# Hornbill.net
KiCad netlist of a schematic drawn in EAGLE
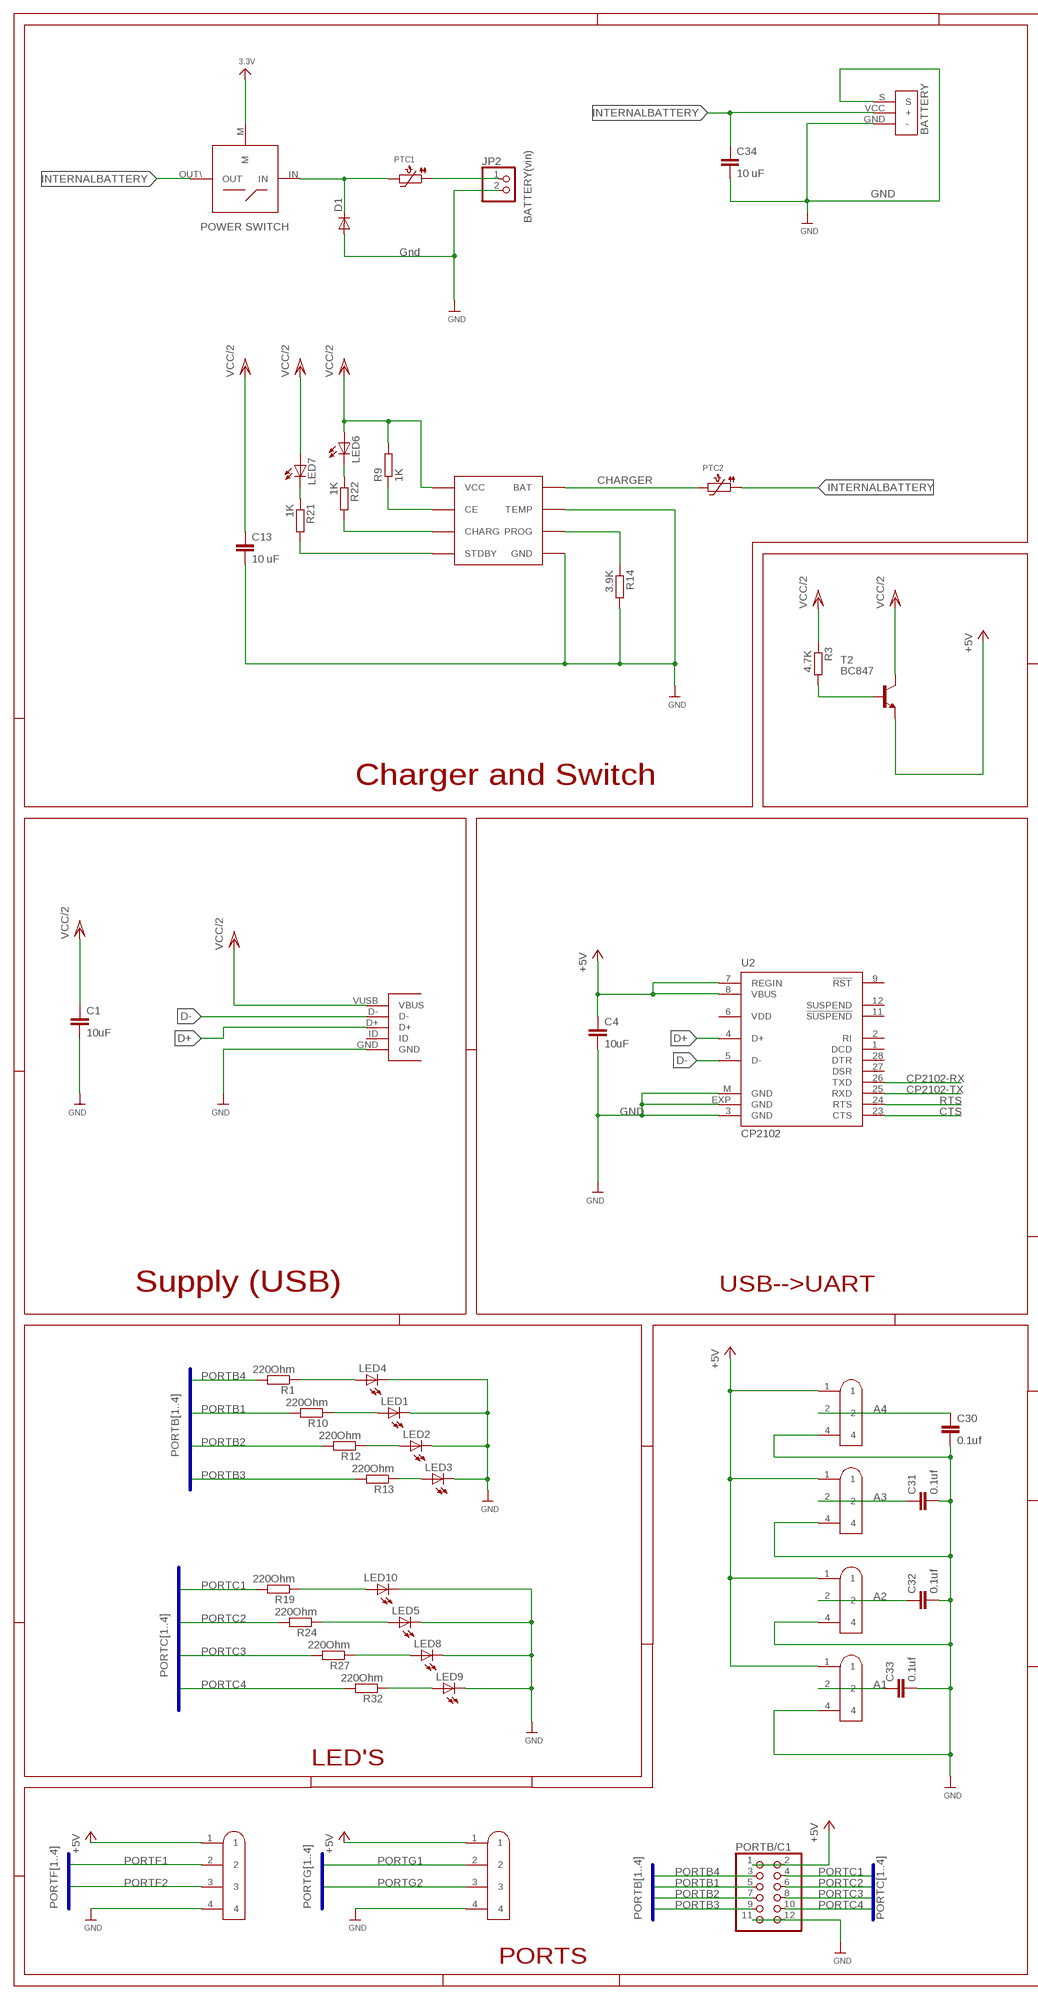
[diagram p0: schematic, sheet 1, part 1 of 2]
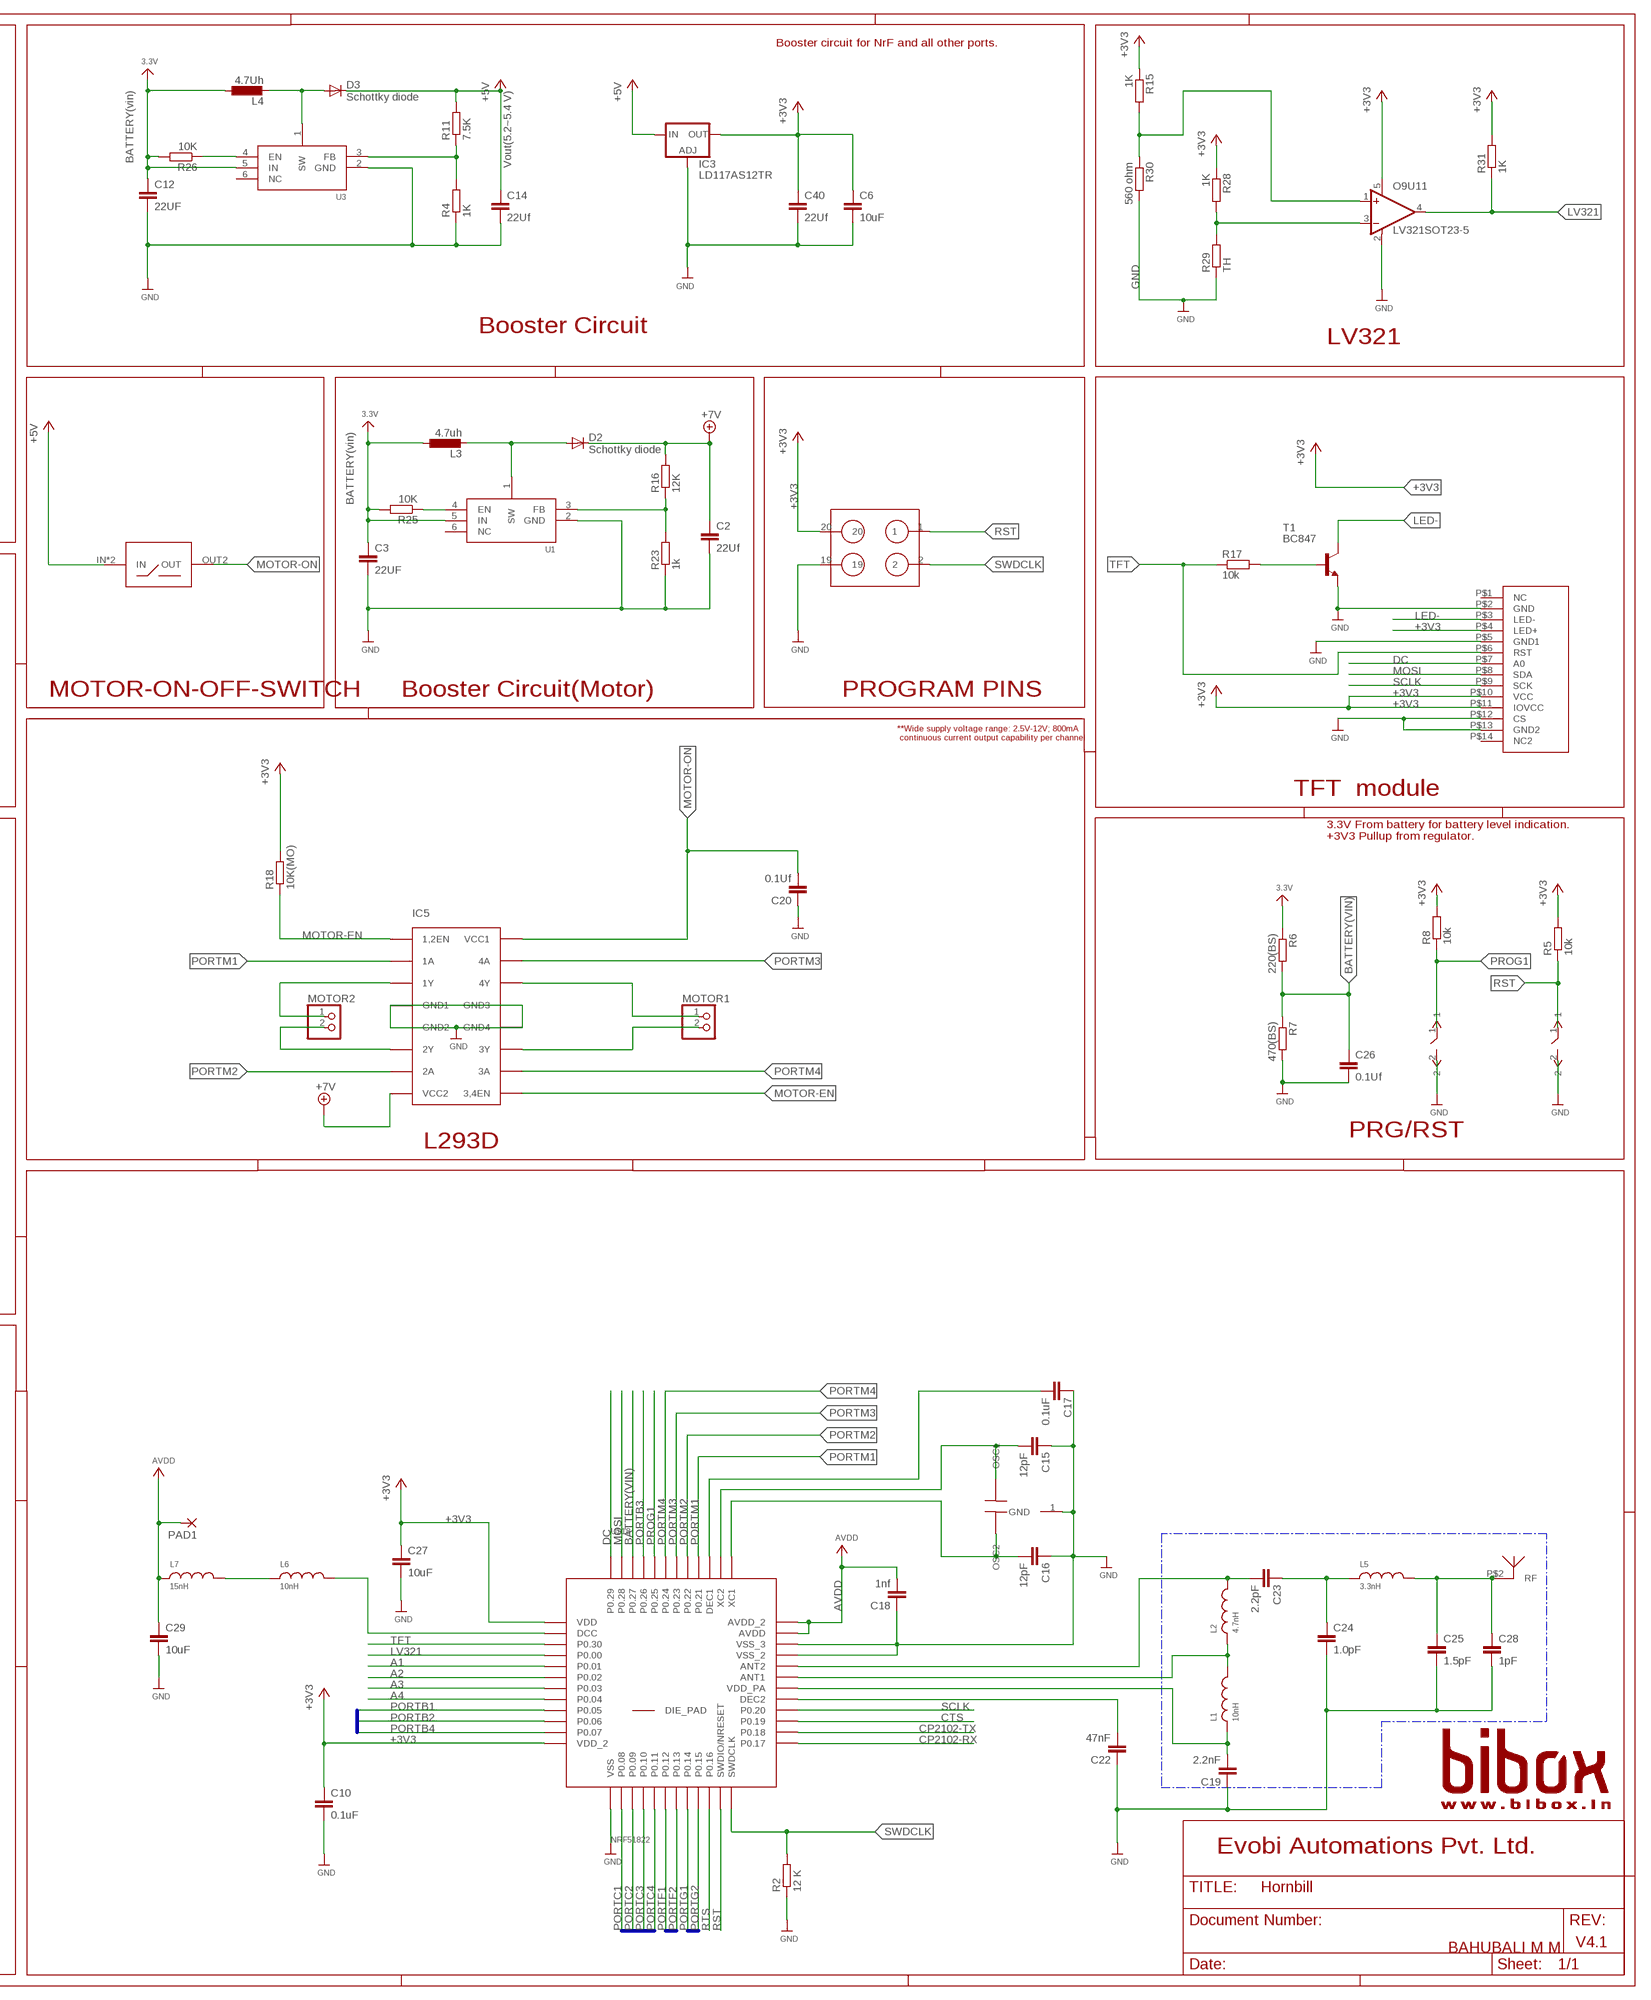
[diagram p1: schematic, sheet 1, part 2 of 2]

(export (version "E")
  (design (tool "Eeschema 10.0.6"))
  (components
    (comp (ref "BATTERY")
      (value "BS")
      (footprint "eagle-import:BS")
      (libsource (lib "eagle-import") (part "BS"))
    )
    (comp (ref "C1")
      (value "10uF")
      (footprint "eagle-import:0603")
      (libsource (lib "eagle-import") (part "CAP0603"))
    )
    (comp (ref "C2")
      (value "22Uf")
      (footprint "eagle-import:C0603")
      (libsource (lib "eagle-import") (part "C-EUC0603"))
    )
    (comp (ref "C3")
      (value "22UF")
      (footprint "eagle-import:C0603")
      (libsource (lib "eagle-import") (part "C-EUC0603"))
    )
    (comp (ref "C4")
      (value "10uF")
      (footprint "eagle-import:0603")
      (libsource (lib "eagle-import") (part "CAP0603"))
    )
    (comp (ref "C6")
      (value "10uF")
      (footprint "eagle-import:C0603")
      (libsource (lib "eagle-import") (part "C-EUC0603"))
    )
    (comp (ref "C10")
      (value "0.1uF")
      (footprint "eagle-import:C0603")
      (libsource (lib "eagle-import") (part "C-EUC0603"))
    )
    (comp (ref "C12")
      (value "22UF")
      (footprint "eagle-import:C0603")
      (libsource (lib "eagle-import") (part "C-EUC0603"))
    )
    (comp (ref "C13")
      (value "10 uF")
      (footprint "eagle-import:C0603")
      (libsource (lib "eagle-import") (part "C-EUC0603"))
    )
    (comp (ref "C14")
      (value "22Uf")
      (footprint "eagle-import:C0603")
      (libsource (lib "eagle-import") (part "C-EUC0603"))
    )
    (comp (ref "C15")
      (value "12pF")
      (footprint "eagle-import:C0603")
      (libsource (lib "eagle-import") (part "C-EUC0603"))
    )
    (comp (ref "C16")
      (value "12pF")
      (footprint "eagle-import:C0603")
      (libsource (lib "eagle-import") (part "C-EUC0603"))
    )
    (comp (ref "C17")
      (value "0.1uF")
      (footprint "eagle-import:C0603")
      (libsource (lib "eagle-import") (part "C-EUC0603"))
    )
    (comp (ref "C18")
      (value "1nf")
      (footprint "eagle-import:C0603")
      (libsource (lib "eagle-import") (part "C-EUC0603"))
    )
    (comp (ref "C19")
      (value "2.2nF")
      (footprint "eagle-import:C0603")
      (libsource (lib "eagle-import") (part "C-EUC0603"))
    )
    (comp (ref "C20")
      (value "0.1Uf")
      (footprint "eagle-import:C0603")
      (libsource (lib "eagle-import") (part "C-EUC0603"))
    )
    (comp (ref "C22")
      (value "47nF")
      (footprint "eagle-import:C0603")
      (libsource (lib "eagle-import") (part "C-EUC0603"))
    )
    (comp (ref "C23")
      (value "2.2pF")
      (footprint "eagle-import:C0603")
      (libsource (lib "eagle-import") (part "C-EUC0603"))
    )
    (comp (ref "C24")
      (value "1.0pF")
      (footprint "eagle-import:C0603")
      (libsource (lib "eagle-import") (part "C-EUC0603"))
    )
    (comp (ref "C25")
      (value "1.5pF")
      (footprint "eagle-import:C0603")
      (libsource (lib "eagle-import") (part "C-EUC0603"))
    )
    (comp (ref "C26")
      (value "0.1Uf")
      (footprint "eagle-import:C0603")
      (libsource (lib "eagle-import") (part "C-EUC0603"))
    )
    (comp (ref "C27")
      (value "10uF")
      (footprint "eagle-import:C0603")
      (libsource (lib "eagle-import") (part "C-EUC0603"))
    )
    (comp (ref "C28")
      (value "1pF")
      (footprint "eagle-import:C0603")
      (libsource (lib "eagle-import") (part "C-EUC0603"))
    )
    (comp (ref "C29")
      (value "10uF")
      (footprint "eagle-import:C0603")
      (libsource (lib "eagle-import") (part "C-EUC0603"))
    )
    (comp (ref "C30")
      (value "0.1uf")
      (footprint "eagle-import:C0603")
      (libsource (lib "eagle-import") (part "C-EUC0603"))
    )
    (comp (ref "C31")
      (value "0.1uf")
      (footprint "eagle-import:C0603")
      (libsource (lib "eagle-import") (part "C-EUC0603"))
    )
    (comp (ref "C32")
      (value "0.1uf")
      (footprint "eagle-import:C0603")
      (libsource (lib "eagle-import") (part "C-EUC0603"))
    )
    (comp (ref "C33")
      (value "0.1uf")
      (footprint "eagle-import:C0603")
      (libsource (lib "eagle-import") (part "C-EUC0603"))
    )
    (comp (ref "C34")
      (value "10 uF")
      (footprint "eagle-import:C0603")
      (libsource (lib "eagle-import") (part "C-EUC0603"))
    )
    (comp (ref "C40")
      (value "22Uf")
      (footprint "eagle-import:C0603")
      (libsource (lib "eagle-import") (part "C-EUC0603"))
    )
    (comp (ref "D1")
      (value "DIODESMA")
      (footprint "eagle-import:SMA-DIODE")
      (libsource (lib "eagle-import") (part "DIODESMA"))
    )
    (comp (ref "D2")
      (value "Schottky diode")
      (footprint "eagle-import:SMA-DIODE")
      (libsource (lib "eagle-import") (part "DIODESMA"))
    )
    (comp (ref "D3")
      (value "Schottky diode")
      (footprint "eagle-import:SMA-DIODE")
      (libsource (lib "eagle-import") (part "DIODESMA"))
    )
    (comp (ref "IC2")
      (value "LT1173CS8")
      (footprint "eagle-import:SOIC8")
      (libsource (lib "eagle-import") (part "LT1173CS8"))
    )
    (comp (ref "IC3")
      (value "LD117AS12TR")
      (footprint "eagle-import:SOT223")
      (libsource (lib "eagle-import") (part "LD117A?S12TR"))
    )
    (comp (ref "IC5")
      (value "L293D")
      (footprint "eagle-import:DIL16")
      (libsource (lib "eagle-import") (part "L293D"))
    )
    (comp (ref "JP2")
      (value "PINHD-1X2")
      (footprint "eagle-import:1X02")
      (libsource (lib "eagle-import") (part "PINHD-1X2"))
    )
    (comp (ref "L1")
      (value "10nH")
      (footprint "eagle-import:0603")
      (libsource (lib "eagle-import") (part "INDUCTOR0603"))
    )
    (comp (ref "L2")
      (value "4.7nH")
      (footprint "eagle-import:0603")
      (libsource (lib "eagle-import") (part "INDUCTOR0603"))
    )
    (comp (ref "L3")
      (value "4.7uh")
      (footprint "eagle-import:POWER-CHOKE_WE-TPC")
      (libsource (lib "eagle-import") (part "L-EUWE-TPC"))
    )
    (comp (ref "L4")
      (value "4.7Uh")
      (footprint "eagle-import:POWER-CHOKE_WE-TPC")
      (libsource (lib "eagle-import") (part "L-EUWE-TPC"))
    )
    (comp (ref "L5")
      (value "3.3nH")
      (footprint "eagle-import:0603")
      (libsource (lib "eagle-import") (part "INDUCTOR0603"))
    )
    (comp (ref "L6")
      (value "10nH")
      (footprint "eagle-import:0603")
      (libsource (lib "eagle-import") (part "INDUCTOR0603"))
    )
    (comp (ref "L7")
      (value "15nH")
      (footprint "eagle-import:0603")
      (libsource (lib "eagle-import") (part "INDUCTOR0603"))
    )
    (comp (ref "LED1")
      (value "LEDCHIP-LED0805")
      (footprint "eagle-import:CHIP-LED0805")
      (libsource (lib "eagle-import") (part "LEDCHIP-LED0805"))
    )
    (comp (ref "LED2")
      (value "LEDCHIP-LED0805")
      (footprint "eagle-import:CHIP-LED0805")
      (libsource (lib "eagle-import") (part "LEDCHIP-LED0805"))
    )
    (comp (ref "LED3")
      (value "LEDCHIP-LED0805")
      (footprint "eagle-import:CHIP-LED0805")
      (libsource (lib "eagle-import") (part "LEDCHIP-LED0805"))
    )
    (comp (ref "LED4")
      (value "LEDCHIP-LED0805")
      (footprint "eagle-import:CHIP-LED0805")
      (libsource (lib "eagle-import") (part "LEDCHIP-LED0805"))
    )
    (comp (ref "LED5")
      (value "LEDCHIP-LED0805")
      (footprint "eagle-import:CHIP-LED0805")
      (libsource (lib "eagle-import") (part "LEDCHIP-LED0805"))
    )
    (comp (ref "LED6")
      (value "LEDCHIP-LED0805")
      (footprint "eagle-import:CHIP-LED0805")
      (libsource (lib "eagle-import") (part "LEDCHIP-LED0805"))
    )
    (comp (ref "LED7")
      (value "LEDCHIP-LED0805")
      (footprint "eagle-import:CHIP-LED0805")
      (libsource (lib "eagle-import") (part "LEDCHIP-LED0805"))
    )
    (comp (ref "LED8")
      (value "LEDCHIP-LED0805")
      (footprint "eagle-import:CHIP-LED0805")
      (libsource (lib "eagle-import") (part "LEDCHIP-LED0805"))
    )
    (comp (ref "LED9")
      (value "LEDCHIP-LED0805")
      (footprint "eagle-import:CHIP-LED0805")
      (libsource (lib "eagle-import") (part "LEDCHIP-LED0805"))
    )
    (comp (ref "LED10")
      (value "LEDCHIP-LED0805")
      (footprint "eagle-import:CHIP-LED0805")
      (libsource (lib "eagle-import") (part "LEDCHIP-LED0805"))
    )
    (comp (ref "MOTOR1")
      (value "PINHD-1X2")
      (footprint "eagle-import:1X02")
      (libsource (lib "eagle-import") (part "PINHD-1X2"))
    )
    (comp (ref "MOTOR2")
      (value "PINHD-1X2")
      (footprint "eagle-import:1X02")
      (libsource (lib "eagle-import") (part "PINHD-1X2"))
    )
    (comp (ref "O9U11")
      (value "LV321SOT23-5")
      (footprint "eagle-import:SOT23-5")
      (libsource (lib "eagle-import") (part "LV321SOT23-5"))
    )
    (comp (ref "PAD1")
      (value "SMD2")
      (footprint "eagle-import:SMD1,27-2,54")
      (libsource (lib "eagle-import") (part "SMD2"))
    )
    (comp (ref "PORTB/C1")
      (value "PINHD-2X6")
      (footprint "eagle-import:2X06")
      (libsource (lib "eagle-import") (part "PINHD-2X6"))
    )
    (comp (ref "PTC1")
      (value "PTC1206")
      (footprint "eagle-import:1206")
      (libsource (lib "eagle-import") (part "PTC1206"))
    )
    (comp (ref "PTC2")
      (value "PTC1206")
      (footprint "eagle-import:1206")
      (libsource (lib "eagle-import") (part "PTC1206"))
    )
    (comp (ref "R1")
      (value "220Ohm")
      (footprint "eagle-import:R0603")
      (libsource (lib "eagle-import") (part "R-EU_R0603"))
    )
    (comp (ref "R2")
      (value "12 K")
      (footprint "eagle-import:R0603")
      (libsource (lib "eagle-import") (part "R-EU_R0603"))
    )
    (comp (ref "R3")
      (value "4.7K")
      (footprint "eagle-import:R0603")
      (libsource (lib "eagle-import") (part "R-EU_R0603"))
    )
    (comp (ref "R4")
      (value "1K")
      (footprint "eagle-import:R0603")
      (libsource (lib "eagle-import") (part "R-EU_R0603"))
    )
    (comp (ref "R5")
      (value "10k")
      (footprint "eagle-import:R0603")
      (libsource (lib "eagle-import") (part "R-EU_R0603"))
    )
    (comp (ref "R6")
      (value "220(BS)")
      (footprint "eagle-import:R0603")
      (libsource (lib "eagle-import") (part "R-EU_R0603"))
    )
    (comp (ref "R7")
      (value "470(BS)")
      (footprint "eagle-import:R0603")
      (libsource (lib "eagle-import") (part "R-EU_R0603"))
    )
    (comp (ref "R8")
      (value "10k")
      (footprint "eagle-import:R0603")
      (libsource (lib "eagle-import") (part "R-EU_R0603"))
    )
    (comp (ref "R9")
      (value "1K")
      (footprint "eagle-import:R0603")
      (libsource (lib "eagle-import") (part "R-EU_R0603"))
    )
    (comp (ref "R10")
      (value "220Ohm")
      (footprint "eagle-import:R0603")
      (libsource (lib "eagle-import") (part "R-EU_R0603"))
    )
    (comp (ref "R11")
      (value "7.5K")
      (footprint "eagle-import:R0603")
      (libsource (lib "eagle-import") (part "R-EU_R0603"))
    )
    (comp (ref "R12")
      (value "220Ohm")
      (footprint "eagle-import:R0603")
      (libsource (lib "eagle-import") (part "R-EU_R0603"))
    )
    (comp (ref "R13")
      (value "220Ohm")
      (footprint "eagle-import:R0603")
      (libsource (lib "eagle-import") (part "R-EU_R0603"))
    )
    (comp (ref "R14")
      (value "3.9K")
      (footprint "eagle-import:R0603")
      (libsource (lib "eagle-import") (part "R-EU_R0603"))
    )
    (comp (ref "R15")
      (value "1K")
      (footprint "eagle-import:R0603")
      (libsource (lib "eagle-import") (part "R-EU_R0603"))
    )
    (comp (ref "R16")
      (value "12K")
      (footprint "eagle-import:R0603")
      (libsource (lib "eagle-import") (part "R-EU_R0603"))
    )
    (comp (ref "R17")
      (value "10k")
      (footprint "eagle-import:R0603")
      (libsource (lib "eagle-import") (part "R-EU_R0603"))
    )
    (comp (ref "R18")
      (value "10K(MO)")
      (footprint "eagle-import:R0603")
      (libsource (lib "eagle-import") (part "R-EU_R0603"))
    )
    (comp (ref "R19")
      (value "220Ohm")
      (footprint "eagle-import:R0603")
      (libsource (lib "eagle-import") (part "R-EU_R0603"))
    )
    (comp (ref "R21")
      (value "1K")
      (footprint "eagle-import:R0603")
      (libsource (lib "eagle-import") (part "R-EU_R0603"))
    )
    (comp (ref "R22")
      (value "1K")
      (footprint "eagle-import:R0603")
      (libsource (lib "eagle-import") (part "R-EU_R0603"))
    )
    (comp (ref "R23")
      (value "1k")
      (footprint "eagle-import:R0603")
      (libsource (lib "eagle-import") (part "R-EU_R0603"))
    )
    (comp (ref "R24")
      (value "220Ohm")
      (footprint "eagle-import:R0603")
      (libsource (lib "eagle-import") (part "R-EU_R0603"))
    )
    (comp (ref "R25")
      (value "10K")
      (footprint "eagle-import:R0603")
      (libsource (lib "eagle-import") (part "R-EU_R0603"))
    )
    (comp (ref "R26")
      (value "10K")
      (footprint "eagle-import:R0603")
      (libsource (lib "eagle-import") (part "R-EU_R0603"))
    )
    (comp (ref "R27")
      (value "220Ohm")
      (footprint "eagle-import:R0603")
      (libsource (lib "eagle-import") (part "R-EU_R0603"))
    )
    (comp (ref "R28")
      (value "1K")
      (footprint "eagle-import:R0603")
      (libsource (lib "eagle-import") (part "R-EU_R0603"))
    )
    (comp (ref "R29")
      (value "TH")
      (footprint "eagle-import:R0805")
      (libsource (lib "eagle-import") (part "R-EU_R0805"))
    )
    (comp (ref "R30")
      (value "560 ohm")
      (footprint "eagle-import:R0603")
      (libsource (lib "eagle-import") (part "R-EU_R0603"))
    )
    (comp (ref "R31")
      (value "1K")
      (footprint "eagle-import:R0603")
      (libsource (lib "eagle-import") (part "R-EU_R0603"))
    )
    (comp (ref "R32")
      (value "220Ohm")
      (footprint "eagle-import:R0603")
      (libsource (lib "eagle-import") (part "R-EU_R0603"))
    )
    (comp (ref "RST")
      (value "NANOSMD\\")
      (footprint "eagle-import:NANOSMD")
      (libsource (lib "eagle-import") (part "NANOSMD{backslash}"))
    )
    (comp (ref "T1")
      (value "BC847")
      (footprint "eagle-import:SOT23")
      (libsource (lib "eagle-import") (part "BC847"))
    )
    (comp (ref "T2")
      (value "BC847")
      (footprint "eagle-import:SOT23")
      (libsource (lib "eagle-import") (part "BC847"))
    )
    (comp (ref "U$4")
      (value "CRYSTAL8MHZ")
      (footprint "eagle-import:8MHZ")
      (libsource (lib "eagle-import") (part "CRYSTAL8MHZ"))
    )
    (comp (ref "U$6")
      (value "10X2")
      (footprint "eagle-import:10X2")
      (libsource (lib "eagle-import") (part "10X2"))
    )
    (comp (ref "U$8")
      (value "SWITCH")
      (footprint "eagle-import:3PINSWITCH@1")
      (libsource (lib "eagle-import") (part "ploul Switch. for nano bulb_SWITCH"))
    )
    (comp (ref "U$9")
      (value "SWITCH")
      (footprint "eagle-import:3PINSWITCH")
      (libsource (lib "eagle-import") (part "SWITCH"))
    )
    (comp (ref "U$18")
      (value "NRF51822")
      (footprint "eagle-import:QFN48")
      (libsource (lib "eagle-import") (part "NRF51822"))
    )
    (comp (ref "U$19")
      (value "3.5MM-JACK")
      (footprint "eagle-import:3.5MM-JACK")
      (libsource (lib "eagle-import") (part "3.5mm jack(4 pole)_3.5MM-JACK"))
    )
    (comp (ref "U$20")
      (value "3.5MM-JACK")
      (footprint "eagle-import:3.5MM-JACK")
      (libsource (lib "eagle-import") (part "3.5mm jack(4 pole)_3.5MM-JACK"))
    )
    (comp (ref "U$26")
      (value "LCDDISPLAY1CHAINA")
      (footprint "eagle-import:LCDDISPLAY1")
      (libsource (lib "eagle-import") (part "LCDDISPLAY1CHAINA"))
    )
    (comp (ref "U$27")
      (value "NANOSMD\\")
      (footprint "eagle-import:NANOSMD")
      (libsource (lib "eagle-import") (part "NANOSMD{backslash}"))
    )
    (comp (ref "U$28")
      (value "3.5MM-JACK")
      (footprint "eagle-import:3.5MM-JACK")
      (libsource (lib "eagle-import") (part "3.5MM-JACK"))
    )
    (comp (ref "U$32")
      (value "3.5MM-JACK")
      (footprint "eagle-import:3.5MM-JACK")
      (libsource (lib "eagle-import") (part "3.5MM-JACK"))
    )
    (comp (ref "U$34")
      (value "3.5MM-JACK")
      (footprint "eagle-import:3.5MM-JACK")
      (libsource (lib "eagle-import") (part "3.5MM-JACK"))
    )
    (comp (ref "U$36")
      (value "3.5MM-JACK")
      (footprint "eagle-import:3.5MM-JACK")
      (libsource (lib "eagle-import") (part "3.5MM-JACK"))
    )
    (comp (ref "U$40")
      (value "WTBT")
      (footprint "eagle-import:BTWT")
      (libsource (lib "eagle-import") (part "WTBT"))
    )
    (comp (ref "U$52")
      (value "USBMICRO")
      (footprint "eagle-import:USBMICRO")
      (libsource (lib "eagle-import") (part "USBMICRO"))
    )
    (comp (ref "U1")
      (value "MIC5320")
      (footprint "eagle-import:SOT23-6")
      (libsource (lib "eagle-import") (part "MIC5320"))
    )
    (comp (ref "U2")
      (value "CP2102")
      (footprint "eagle-import:MLP28")
      (libsource (lib "eagle-import") (part "CP210X_USB_UART"))
    )
    (comp (ref "U3")
      (value "MIC5320")
      (footprint "eagle-import:SOT23-6")
      (libsource (lib "eagle-import") (part "MIC5320"))
    )
  )
  (nets
    (net (code "5") (name "+3V3") (class "Default")
      (node (ref "C10") (pin "1") (pinfunction "1_1") (pintype "passive"))
      (node (ref "C27") (pin "1") (pinfunction "1_1") (pintype "passive"))
      (node (ref "C40") (pin "1") (pinfunction "1_1") (pintype "passive"))
      (node (ref "C6") (pin "1") (pinfunction "1_1") (pintype "passive"))
      (node (ref "IC3") (pin "4") (pinfunction "OUT_4") (pintype "passive"))
      (node (ref "O9U11") (pin "5") (pinfunction "V+_5") (pintype "power_in"))
      (node (ref "R15") (pin "1") (pinfunction "1_1") (pintype "passive"))
      (node (ref "R18") (pin "2") (pinfunction "2_2") (pintype "passive"))
      (node (ref "R28") (pin "1") (pinfunction "1_1") (pintype "passive"))
      (node (ref "R31") (pin "2") (pinfunction "2_2") (pintype "passive"))
      (node (ref "R5") (pin "2") (pinfunction "2_2") (pintype "passive"))
      (node (ref "R8") (pin "2") (pinfunction "2_2") (pintype "passive"))
      (node (ref "U$18") (pin "1") (pinfunction "VDD_1") (pintype "bidirectional"))
      (node (ref "U$18") (pin "12") (pinfunction "VDD_2_12") (pintype "bidirectional"))
      (node (ref "U$26") (pin "P$10") (pinfunction "VCC_P$10") (pintype "bidirectional"))
      (node (ref "U$26") (pin "P$11") (pinfunction "IOVCC_P$11") (pintype "bidirectional"))
      (node (ref "U$26") (pin "P$4") (pinfunction "LED+_P$4") (pintype "bidirectional"))
      (node (ref "U$6") (pin "20") (pinfunction "20_20") (pintype "bidirectional"))
    )
    (net (code "6") (name "+5V") (class "Default")
      (node (ref "C14") (pin "1") (pinfunction "1_1") (pintype "passive"))
      (node (ref "C4") (pin "1") (pinfunction "1_1") (pintype "passive"))
      (node (ref "D3") (pin "C") (pinfunction "C_C") (pintype "passive"))
      (node (ref "IC3") (pin "3") (pinfunction "IN_3") (pintype "input"))
      (node (ref "PORTB/C1") (pin "1") (pinfunction "1_1") (pintype "passive"))
      (node (ref "PORTB/C1") (pin "2") (pinfunction "2_2") (pintype "passive"))
      (node (ref "R11") (pin "2") (pinfunction "2_2") (pintype "passive"))
      (node (ref "T2") (pin "2") (pinfunction "E_2") (pintype "passive"))
      (node (ref "U$19") (pin "1") (pinfunction "1_1") (pintype "bidirectional"))
      (node (ref "U$20") (pin "1") (pinfunction "1_1") (pintype "bidirectional"))
      (node (ref "U$28") (pin "1") (pinfunction "1_1") (pintype "bidirectional"))
      (node (ref "U$32") (pin "1") (pinfunction "1_1") (pintype "bidirectional"))
      (node (ref "U$34") (pin "1") (pinfunction "1_1") (pintype "bidirectional"))
      (node (ref "U$36") (pin "1") (pinfunction "1_1") (pintype "bidirectional"))
      (node (ref "U$8") (pin "IN") (pinfunction "IN_IN") (pintype "bidirectional"))
      (node (ref "U$8") (pin "OUT1") (pinfunction "IN_OUT1") (pintype "bidirectional"))
      (node (ref "U2") (pin "7") (pinfunction "REGIN_7") (pintype "passive"))
      (node (ref "U2") (pin "8") (pinfunction "VBUS_8") (pintype "input"))
    )
    (net (code "7") (name "+7V") (class "Default")
      (node (ref "C2") (pin "1") (pinfunction "1_1") (pintype "passive"))
      (node (ref "D2") (pin "C") (pinfunction "C_C") (pintype "passive"))
      (node (ref "IC5") (pin "8") (pinfunction "VCC2_8") (pintype "power_in"))
      (node (ref "R16") (pin "2") (pinfunction "2_2") (pintype "passive"))
    )
    (net (code "8") (name "/A1") (class "Default")
      (node (ref "C33") (pin "1") (pinfunction "1_1") (pintype "passive"))
      (node (ref "U$18") (pin "5") (pinfunction "P0.01_5") (pintype "bidirectional"))
      (node (ref "U$34") (pin "2") (pinfunction "2_2") (pintype "bidirectional"))
    )
    (net (code "9") (name "/A2") (class "Default")
      (node (ref "C32") (pin "1") (pinfunction "1_1") (pintype "passive"))
      (node (ref "U$18") (pin "6") (pinfunction "P0.02_6") (pintype "bidirectional"))
      (node (ref "U$36") (pin "2") (pinfunction "2_2") (pintype "bidirectional"))
    )
    (net (code "10") (name "/A3") (class "Default")
      (node (ref "C31") (pin "1") (pinfunction "1_1") (pintype "passive"))
      (node (ref "U$18") (pin "7") (pinfunction "P0.03_7") (pintype "bidirectional"))
      (node (ref "U$32") (pin "2") (pinfunction "2_2") (pintype "bidirectional"))
    )
    (net (code "11") (name "/A4") (class "Default")
      (node (ref "C30") (pin "1") (pinfunction "1_1") (pintype "passive"))
      (node (ref "U$18") (pin "8") (pinfunction "P0.04_8") (pintype "bidirectional"))
      (node (ref "U$28") (pin "2") (pinfunction "2_2") (pintype "bidirectional"))
    )
    (net (code "12") (name "/CHARGER") (class "Default")
      (node (ref "IC2") (pin "BAT") (pinfunction "BAT_BAT") (pintype "power_in"))
      (node (ref "PTC2") (pin "2") (pinfunction "2_2") (pintype "passive"))
    )
    (net (code "13") (name "/CP2102-RX") (class "Default")
      (node (ref "U$18") (pin "25") (pinfunction "P0.17_25") (pintype "bidirectional"))
      (node (ref "U2") (pin "26") (pinfunction "TXD_26") (pintype "output"))
    )
    (net (code "14") (name "/CP2102-TX") (class "Default")
      (node (ref "U$18") (pin "26") (pinfunction "P0.18_26") (pintype "bidirectional"))
      (node (ref "U2") (pin "25") (pinfunction "RXD_25") (pintype "input"))
    )
    (net (code "15") (name "/CTS") (class "Default")
      (node (ref "U$18") (pin "27") (pinfunction "P0.19_27") (pintype "bidirectional"))
      (node (ref "U2") (pin "23") (pinfunction "CTS_23") (pintype "input"))
    )
    (net (code "16") (name "/DC") (class "Default")
      (node (ref "U$18") (pin "48") (pinfunction "P0.29_48") (pintype "bidirectional"))
      (node (ref "U$26") (pin "P$7") (pinfunction "A0_P$7") (pintype "bidirectional"))
    )
    (net (code "17") (name "/MOSI") (class "Default")
      (node (ref "U$18") (pin "47") (pinfunction "P0.28_47") (pintype "bidirectional"))
      (node (ref "U$26") (pin "P$8") (pinfunction "SDA_P$8") (pintype "bidirectional"))
    )
    (net (code "18") (name "/PORTB1") (class "Default")
      (node (ref "PORTB/C1") (pin "5") (pinfunction "5_5") (pintype "passive"))
      (node (ref "R10") (pin "2") (pinfunction "2_2") (pintype "passive"))
      (node (ref "U$18") (pin "9") (pinfunction "P0.05_9") (pintype "bidirectional"))
    )
    (net (code "19") (name "/PORTB2") (class "Default")
      (node (ref "PORTB/C1") (pin "7") (pinfunction "7_7") (pintype "passive"))
      (node (ref "R12") (pin "2") (pinfunction "2_2") (pintype "passive"))
      (node (ref "U$18") (pin "10") (pinfunction "P0.06_10") (pintype "bidirectional"))
    )
    (net (code "20") (name "/PORTB3") (class "Default")
      (node (ref "PORTB/C1") (pin "9") (pinfunction "9_9") (pintype "passive"))
      (node (ref "R13") (pin "2") (pinfunction "2_2") (pintype "passive"))
      (node (ref "U$18") (pin "45") (pinfunction "P0.26_45") (pintype "bidirectional"))
    )
    (net (code "21") (name "/PORTB4") (class "Default")
      (node (ref "PORTB/C1") (pin "3") (pinfunction "3_3") (pintype "passive"))
      (node (ref "R1") (pin "2") (pinfunction "2_2") (pintype "passive"))
      (node (ref "U$18") (pin "11") (pinfunction "P0.07_11") (pintype "bidirectional"))
    )
    (net (code "23") (name "/PORTC1") (class "Default")
      (node (ref "PORTB/C1") (pin "4") (pinfunction "4_4") (pintype "passive"))
      (node (ref "R19") (pin "2") (pinfunction "2_2") (pintype "passive"))
      (node (ref "U$18") (pin "14") (pinfunction "P0.08_14") (pintype "bidirectional"))
    )
    (net (code "24") (name "/PORTC2") (class "Default")
      (node (ref "PORTB/C1") (pin "6") (pinfunction "6_6") (pintype "passive"))
      (node (ref "R24") (pin "2") (pinfunction "2_2") (pintype "passive"))
      (node (ref "U$18") (pin "15") (pinfunction "P0.09_15") (pintype "bidirectional"))
    )
    (net (code "25") (name "/PORTC3") (class "Default")
      (node (ref "PORTB/C1") (pin "8") (pinfunction "8_8") (pintype "passive"))
      (node (ref "R27") (pin "2") (pinfunction "2_2") (pintype "passive"))
      (node (ref "U$18") (pin "16") (pinfunction "P0.10_16") (pintype "bidirectional"))
    )
    (net (code "26") (name "/PORTC4") (class "Default")
      (node (ref "PORTB/C1") (pin "10") (pinfunction "10_10") (pintype "passive"))
      (node (ref "R32") (pin "2") (pinfunction "2_2") (pintype "passive"))
      (node (ref "U$18") (pin "17") (pinfunction "P0.11_17") (pintype "bidirectional"))
    )
    (net (code "28") (name "/PORTF1") (class "Default")
      (node (ref "U$18") (pin "18") (pinfunction "P0.12_18") (pintype "bidirectional"))
      (node (ref "U$20") (pin "2") (pinfunction "2_2") (pintype "bidirectional"))
    )
    (net (code "29") (name "/PORTF2") (class "Default")
      (node (ref "U$18") (pin "19") (pinfunction "P0.13_19") (pintype "bidirectional"))
      (node (ref "U$20") (pin "3") (pinfunction "3_3") (pintype "bidirectional"))
    )
    (net (code "31") (name "/PORTG1") (class "Default")
      (node (ref "U$18") (pin "20") (pinfunction "P0.14_20") (pintype "bidirectional"))
      (node (ref "U$19") (pin "2") (pinfunction "2_2") (pintype "bidirectional"))
    )
    (net (code "32") (name "/PORTG2") (class "Default")
      (node (ref "U$18") (pin "21") (pinfunction "P0.15_21") (pintype "bidirectional"))
      (node (ref "U$19") (pin "3") (pinfunction "3_3") (pintype "bidirectional"))
    )
    (net (code "34") (name "/RTS") (class "Default")
      (node (ref "U$18") (pin "22") (pinfunction "P0.16_22") (pintype "bidirectional"))
      (node (ref "U2") (pin "24") (pinfunction "RTS_24") (pintype "output"))
    )
    (net (code "35") (name "/SCLK") (class "Default")
      (node (ref "U$18") (pin "28") (pinfunction "P0.20_28") (pintype "bidirectional"))
      (node (ref "U$26") (pin "P$9") (pinfunction "SCK_P$9") (pintype "bidirectional"))
    )
    (net (code "36") (name "/VDD") (class "Default")
      (node (ref "U2") (pin "6") (pinfunction "VDD_6") (pintype "power_in"))
    )
    (net (code "37") (name "3.3V") (class "Default")
      (node (ref "C12") (pin "1") (pinfunction "1_1") (pintype "passive"))
      (node (ref "C3") (pin "1") (pinfunction "1_1") (pintype "passive"))
      (node (ref "L3") (pin "1") (pinfunction "1_1") (pintype "passive"))
      (node (ref "L4") (pin "1") (pinfunction "1_1") (pintype "passive"))
      (node (ref "R25") (pin "2") (pinfunction "2_2") (pintype "passive"))
      (node (ref "R26") (pin "2") (pinfunction "2_2") (pintype "passive"))
      (node (ref "R6") (pin "1") (pinfunction "1_1") (pintype "passive"))
      (node (ref "U$9") (pin "M") (pinfunction "M_M") (pintype "bidirectional"))
      (node (ref "U1") (pin "5") (pinfunction "IN_5") (pintype "bidirectional"))
      (node (ref "U3") (pin "5") (pinfunction "IN_5") (pintype "bidirectional"))
    )
    (net (code "38") (name "AVDD") (class "Default")
      (node (ref "C18") (pin "2") (pinfunction "2_2") (pintype "passive"))
      (node (ref "C29") (pin "1") (pinfunction "1_1") (pintype "passive"))
      (node (ref "L7") (pin "1") (pinfunction "1_1") (pintype "passive"))
      (node (ref "PAD1") (pin "1") (pinfunction "P_1") (pintype "passive"))
      (node (ref "U$18") (pin "35") (pinfunction "AVDD_35") (pintype "bidirectional"))
      (node (ref "U$18") (pin "36") (pinfunction "AVDD_2_36") (pintype "bidirectional"))
    )
    (net (code "39") (name "BATTERY(VIN)") (class "Default")
      (node (ref "C26") (pin "1") (pinfunction "1_1") (pintype "passive"))
      (node (ref "R6") (pin "2") (pinfunction "2_2") (pintype "passive"))
      (node (ref "R7") (pin "1") (pinfunction "1_1") (pintype "passive"))
      (node (ref "U$18") (pin "46") (pinfunction "P0.27_46") (pintype "bidirectional"))
    )
    (net (code "40") (name "D+") (class "Default")
      (node (ref "U$52") (pin "D+") (pinfunction "D+_D+") (pintype "bidirectional"))
      (node (ref "U2") (pin "4") (pinfunction "D+_4") (pintype "bidirectional"))
    )
    (net (code "41") (name "D-") (class "Default")
      (node (ref "U$52") (pin "D-") (pinfunction "D-_D-") (pintype "bidirectional"))
      (node (ref "U2") (pin "5") (pinfunction "D-_5") (pintype "bidirectional"))
    )
    (net (code "42") (name "GND") (class "Default")
      (node (ref "BATTERY") (pin "GND") (pinfunction "-_GND") (pintype "bidirectional"))
      (node (ref "BATTERY") (pin "S") (pinfunction "S_S") (pintype "bidirectional"))
      (node (ref "C1") (pin "2") (pinfunction "2_2") (pintype "passive"))
      (node (ref "C10") (pin "2") (pinfunction "2_2") (pintype "passive"))
      (node (ref "C12") (pin "2") (pinfunction "2_2") (pintype "passive"))
      (node (ref "C13") (pin "2") (pinfunction "2_2") (pintype "passive"))
      (node (ref "C14") (pin "2") (pinfunction "2_2") (pintype "passive"))
      (node (ref "C15") (pin "1") (pinfunction "1_1") (pintype "passive"))
      (node (ref "C16") (pin "1") (pinfunction "1_1") (pintype "passive"))
      (node (ref "C17") (pin "1") (pinfunction "1_1") (pintype "passive"))
      (node (ref "C18") (pin "1") (pinfunction "1_1") (pintype "passive"))
      (node (ref "C19") (pin "1") (pinfunction "1_1") (pintype "passive"))
      (node (ref "C2") (pin "2") (pinfunction "2_2") (pintype "passive"))
      (node (ref "C20") (pin "1") (pinfunction "1_1") (pintype "passive"))
      (node (ref "C22") (pin "1") (pinfunction "1_1") (pintype "passive"))
      (node (ref "C24") (pin "2") (pinfunction "2_2") (pintype "passive"))
      (node (ref "C25") (pin "2") (pinfunction "2_2") (pintype "passive"))
      (node (ref "C26") (pin "2") (pinfunction "2_2") (pintype "passive"))
      (node (ref "C27") (pin "2") (pinfunction "2_2") (pintype "passive"))
      (node (ref "C28") (pin "2") (pinfunction "2_2") (pintype "passive"))
      (node (ref "C29") (pin "2") (pinfunction "2_2") (pintype "passive"))
      (node (ref "C3") (pin "2") (pinfunction "2_2") (pintype "passive"))
      (node (ref "C30") (pin "2") (pinfunction "2_2") (pintype "passive"))
      (node (ref "C31") (pin "2") (pinfunction "2_2") (pintype "passive"))
      (node (ref "C32") (pin "2") (pinfunction "2_2") (pintype "passive"))
      (node (ref "C33") (pin "2") (pinfunction "2_2") (pintype "passive"))
      (node (ref "C34") (pin "2") (pinfunction "2_2") (pintype "passive"))
      (node (ref "C4") (pin "2") (pinfunction "2_2") (pintype "passive"))
      (node (ref "C40") (pin "2") (pinfunction "2_2") (pintype "passive"))
      (node (ref "C6") (pin "2") (pinfunction "2_2") (pintype "passive"))
      (node (ref "D1") (pin "A") (pinfunction "A_A") (pintype "passive"))
      (node (ref "IC2") (pin "GND") (pinfunction "GND_GND") (pintype "passive"))
      (node (ref "IC2") (pin "TEMP") (pinfunction "TEMP_TEMP") (pintype "passive"))
      (node (ref "IC3") (pin "1") (pinfunction "ADJ_1") (pintype "input"))
      (node (ref "IC5") (pin "12") (pinfunction "GND4_12") (pintype "power_in"))
      (node (ref "IC5") (pin "13") (pinfunction "GND3_13") (pintype "power_in"))
      (node (ref "IC5") (pin "4") (pinfunction "GND1_4") (pintype "power_in"))
      (node (ref "IC5") (pin "5") (pinfunction "GND2_5") (pintype "power_in"))
      (node (ref "JP2") (pin "2") (pinfunction "2_2") (pintype "passive"))
      (node (ref "LED1") (pin "C") (pinfunction "C_C") (pintype "passive"))
      (node (ref "LED10") (pin "C") (pinfunction "C_C") (pintype "passive"))
      (node (ref "LED2") (pin "C") (pinfunction "C_C") (pintype "passive"))
      (node (ref "LED3") (pin "C") (pinfunction "C_C") (pintype "passive"))
      (node (ref "LED4") (pin "C") (pinfunction "C_C") (pintype "passive"))
      (node (ref "LED5") (pin "C") (pinfunction "C_C") (pintype "passive"))
      (node (ref "LED8") (pin "C") (pinfunction "C_C") (pintype "passive"))
      (node (ref "LED9") (pin "C") (pinfunction "C_C") (pintype "passive"))
      (node (ref "O9U11") (pin "2") (pinfunction "V-_2") (pintype "power_in"))
      (node (ref "PORTB/C1") (pin "11") (pinfunction "11_11") (pintype "passive"))
      (node (ref "PORTB/C1") (pin "12") (pinfunction "12_12") (pintype "passive"))
      (node (ref "R14") (pin "2") (pinfunction "2_2") (pintype "passive"))
      (node (ref "R2") (pin "1") (pinfunction "1_1") (pintype "passive"))
      (node (ref "R23") (pin "1") (pinfunction "1_1") (pintype "passive"))
      (node (ref "R29") (pin "1") (pinfunction "1_1") (pintype "passive"))
      (node (ref "R30") (pin "2") (pinfunction "2_2") (pintype "passive"))
      (node (ref "R4") (pin "1") (pinfunction "1_1") (pintype "passive"))
      (node (ref "R7") (pin "2") (pinfunction "2_2") (pintype "passive"))
      (node (ref "RST") (pin "2") (pinfunction "2_2") (pintype "bidirectional"))
      (node (ref "T1") (pin "2") (pinfunction "E_2") (pintype "passive"))
      (node (ref "U$18") (pin "13") (pinfunction "VSS_13") (pintype "bidirectional"))
      (node (ref "U$18") (pin "33") (pinfunction "VSS_2_33") (pintype "bidirectional"))
      (node (ref "U$18") (pin "34") (pinfunction "VSS_3_34") (pintype "bidirectional"))
      (node (ref "U$19") (pin "4") (pinfunction "4_4") (pintype "bidirectional"))
      (node (ref "U$20") (pin "4") (pinfunction "4_4") (pintype "bidirectional"))
      (node (ref "U$26") (pin "P$12") (pinfunction "CS_P$12") (pintype "bidirectional"))
      (node (ref "U$26") (pin "P$13") (pinfunction "GND2_P$13") (pintype "bidirectional"))
      (node (ref "U$26") (pin "P$2") (pinfunction "GND_P$2") (pintype "bidirectional"))
      (node (ref "U$26") (pin "P$5") (pinfunction "GND1_P$5") (pintype "bidirectional"))
      (node (ref "U$27") (pin "2") (pinfunction "2_2") (pintype "bidirectional"))
      (node (ref "U$28") (pin "4") (pinfunction "4_4") (pintype "bidirectional"))
      (node (ref "U$32") (pin "4") (pinfunction "4_4") (pintype "bidirectional"))
      (node (ref "U$34") (pin "4") (pinfunction "4_4") (pintype "bidirectional"))
      (node (ref "U$36") (pin "4") (pinfunction "4_4") (pintype "bidirectional"))
      (node (ref "U$4") (pin "1") (pinfunction "GND_1") (pintype "bidirectional"))
      (node (ref "U$52") (pin "GND") (pinfunction "GND_GND") (pintype "bidirectional"))
      (node (ref "U$6") (pin "19") (pinfunction "19_19") (pintype "bidirectional"))
      (node (ref "U1") (pin "2") (pinfunction "GND_2") (pintype "bidirectional"))
      (node (ref "U2") (pin "3") (pinfunction "GND_3") (pintype "power_in"))
      (node (ref "U2") (pin "EXP") (pinfunction "GND_EXP") (pintype "power_in"))
      (node (ref "U2") (pin "M") (pinfunction "GND_M") (pintype "power_in"))
      (node (ref "U3") (pin "2") (pinfunction "GND_2") (pintype "bidirectional"))
    )
    (net (code "43") (name "INTERNALBATTERY") (class "Default")
      (node (ref "BATTERY") (pin "VCC") (pinfunction "+_VCC") (pintype "bidirectional"))
      (node (ref "C34") (pin "1") (pinfunction "1_1") (pintype "passive"))
      (node (ref "PTC2") (pin "1") (pinfunction "1_1") (pintype "passive"))
      (node (ref "U$9") (pin "OUT\\") (pinfunction "OUT_OUT\\") (pintype "bidirectional"))
    )
    (net (code "44") (name "LED-") (class "Default")
      (node (ref "T1") (pin "3") (pinfunction "C_3") (pintype "passive"))
      (node (ref "U$26") (pin "P$3") (pinfunction "LED-_P$3") (pintype "bidirectional"))
    )
    (net (code "45") (name "LV321") (class "Default")
      (node (ref "O9U11") (pin "4") (pinfunction "OUT_4") (pintype "output"))
      (node (ref "R31") (pin "1") (pinfunction "1_1") (pintype "passive"))
      (node (ref "U$18") (pin "4") (pinfunction "P0.00_4") (pintype "bidirectional"))
    )
    (net (code "46") (name "MOTOR-EN") (class "Default")
      (node (ref "IC5") (pin "1") (pinfunction "1,2EN_1") (pintype "input"))
      (node (ref "IC5") (pin "9") (pinfunction "3,4EN_9") (pintype "input"))
      (node (ref "R18") (pin "1") (pinfunction "1_1") (pintype "passive"))
    )
    (net (code "47") (name "MOTOR-ON") (class "Default")
      (node (ref "C20") (pin "2") (pinfunction "2_2") (pintype "passive"))
      (node (ref "IC5") (pin "16") (pinfunction "VCC1_16") (pintype "power_in"))
      (node (ref "U$8") (pin "OUT2") (pinfunction "OUT_OUT2") (pintype "bidirectional"))
    )
    (net (code "48") (name "Net-(C23-Pad1)") (class "Default")
      (node (ref "C23") (pin "1") (pinfunction "1_1") (pintype "passive"))
      (node (ref "C24") (pin "1") (pinfunction "1_1") (pintype "passive"))
      (node (ref "L5") (pin "1") (pinfunction "1_1") (pintype "passive"))
    )
    (net (code "49") (name "Net-(D1-PadC)") (class "Default")
      (node (ref "D1") (pin "C") (pinfunction "C_C") (pintype "passive"))
      (node (ref "PTC1") (pin "2") (pinfunction "2_2") (pintype "passive"))
      (node (ref "U$9") (pin "IN") (pinfunction "IN_IN") (pintype "bidirectional"))
    )
    (net (code "50") (name "Net-(IC2-CHARG)") (class "Default")
      (node (ref "IC2") (pin "CHRG") (pinfunction "CHARG_CHRG") (pintype "passive"))
      (node (ref "R22") (pin "2") (pinfunction "2_2") (pintype "passive"))
    )
    (net (code "51") (name "Net-(IC2-PadCE)") (class "Default")
      (node (ref "IC2") (pin "CE") (pinfunction "CE_CE") (pintype "passive"))
      (node (ref "R9") (pin "1") (pinfunction "1_1") (pintype "passive"))
    )
    (net (code "52") (name "Net-(IC2-PadPROG)") (class "Default")
      (node (ref "IC2") (pin "PROG") (pinfunction "PROG_PROG") (pintype "passive"))
      (node (ref "R14") (pin "1") (pinfunction "1_1") (pintype "passive"))
    )
    (net (code "53") (name "Net-(IC2-PadSTDBY)") (class "Default")
      (node (ref "IC2") (pin "STDBY") (pinfunction "STDBY_STDBY") (pintype "passive"))
      (node (ref "R21") (pin "2") (pinfunction "2_2") (pintype "passive"))
    )
    (net (code "54") (name "Net-(IC5-1Y)") (class "Default")
      (node (ref "IC5") (pin "3") (pinfunction "1Y_3") (pintype "output"))
      (node (ref "MOTOR2") (pin "1") (pinfunction "1_1") (pintype "passive"))
    )
    (net (code "55") (name "Net-(IC5-2Y)") (class "Default")
      (node (ref "IC5") (pin "6") (pinfunction "2Y_6") (pintype "output"))
      (node (ref "MOTOR2") (pin "2") (pinfunction "2_2") (pintype "passive"))
    )
    (net (code "56") (name "Net-(IC5-3Y)") (class "Default")
      (node (ref "IC5") (pin "11") (pinfunction "3Y_11") (pintype "output"))
      (node (ref "MOTOR1") (pin "2") (pinfunction "2_2") (pintype "passive"))
    )
    (net (code "57") (name "Net-(IC5-4Y)") (class "Default")
      (node (ref "IC5") (pin "14") (pinfunction "4Y_14") (pintype "output"))
      (node (ref "MOTOR1") (pin "1") (pinfunction "1_1") (pintype "passive"))
    )
    (net (code "58") (name "Net-(JP2-Pad1)") (class "Default")
      (node (ref "JP2") (pin "1") (pinfunction "1_1") (pintype "passive"))
      (node (ref "PTC1") (pin "1") (pinfunction "1_1") (pintype "passive"))
    )
    (net (code "59") (name "Net-(L6-Pad1)") (class "Default")
      (node (ref "L6") (pin "1") (pinfunction "1_1") (pintype "passive"))
      (node (ref "L7") (pin "2") (pinfunction "2_2") (pintype "passive"))
    )
    (net (code "60") (name "Net-(LED1-PadA)") (class "Default")
      (node (ref "LED1") (pin "A") (pinfunction "A_A") (pintype "passive"))
      (node (ref "R10") (pin "1") (pinfunction "1_1") (pintype "passive"))
    )
    (net (code "61") (name "Net-(LED2-PadA)") (class "Default")
      (node (ref "LED2") (pin "A") (pinfunction "A_A") (pintype "passive"))
      (node (ref "R12") (pin "1") (pinfunction "1_1") (pintype "passive"))
    )
    (net (code "62") (name "Net-(LED3-PadA)") (class "Default")
      (node (ref "LED3") (pin "A") (pinfunction "A_A") (pintype "passive"))
      (node (ref "R13") (pin "1") (pinfunction "1_1") (pintype "passive"))
    )
    (net (code "63") (name "Net-(LED4-PadA)") (class "Default")
      (node (ref "LED4") (pin "A") (pinfunction "A_A") (pintype "passive"))
      (node (ref "R1") (pin "1") (pinfunction "1_1") (pintype "passive"))
    )
    (net (code "64") (name "Net-(LED5-PadA)") (class "Default")
      (node (ref "LED5") (pin "A") (pinfunction "A_A") (pintype "passive"))
      (node (ref "R24") (pin "1") (pinfunction "1_1") (pintype "passive"))
    )
    (net (code "65") (name "Net-(LED6-PadC)") (class "Default")
      (node (ref "LED6") (pin "C") (pinfunction "C_C") (pintype "passive"))
      (node (ref "R22") (pin "1") (pinfunction "1_1") (pintype "passive"))
    )
    (net (code "66") (name "Net-(LED7-PadC)") (class "Default")
      (node (ref "LED7") (pin "C") (pinfunction "C_C") (pintype "passive"))
      (node (ref "R21") (pin "1") (pinfunction "1_1") (pintype "passive"))
    )
    (net (code "67") (name "Net-(LED8-PadA)") (class "Default")
      (node (ref "LED8") (pin "A") (pinfunction "A_A") (pintype "passive"))
      (node (ref "R27") (pin "1") (pinfunction "1_1") (pintype "passive"))
    )
    (net (code "68") (name "Net-(LED9-PadA)") (class "Default")
      (node (ref "LED9") (pin "A") (pinfunction "A_A") (pintype "passive"))
      (node (ref "R32") (pin "1") (pinfunction "1_1") (pintype "passive"))
    )
    (net (code "69") (name "Net-(LED10-PadA)") (class "Default")
      (node (ref "LED10") (pin "A") (pinfunction "A_A") (pintype "passive"))
      (node (ref "R19") (pin "1") (pinfunction "1_1") (pintype "passive"))
    )
    (net (code "70") (name "Net-(O9U11-+IN)") (class "Default")
      (node (ref "O9U11") (pin "1") (pinfunction "+IN_1") (pintype "input"))
      (node (ref "R15") (pin "2") (pinfunction "2_2") (pintype "passive"))
      (node (ref "R30") (pin "1") (pinfunction "1_1") (pintype "passive"))
    )
    (net (code "71") (name "Net-(O9U11--IN)") (class "Default")
      (node (ref "O9U11") (pin "3") (pinfunction "-IN_3") (pintype "input"))
      (node (ref "R28") (pin "2") (pinfunction "2_2") (pintype "passive"))
      (node (ref "R29") (pin "2") (pinfunction "2_2") (pintype "passive"))
    )
    (net (code "72") (name "Net-(T1-B)") (class "Default")
      (node (ref "R17") (pin "2") (pinfunction "2_2") (pintype "passive"))
      (node (ref "T1") (pin "1") (pinfunction "B_1") (pintype "passive"))
    )
    (net (code "73") (name "Net-(T2-B)") (class "Default")
      (node (ref "R3") (pin "2") (pinfunction "2_2") (pintype "passive"))
      (node (ref "T2") (pin "1") (pinfunction "B_1") (pintype "passive"))
    )
    (net (code "74") (name "Net-(U$18-ANT1)") (class "Default")
      (node (ref "L1") (pin "2") (pinfunction "2_2") (pintype "passive"))
      (node (ref "L2") (pin "1") (pinfunction "1_1") (pintype "passive"))
      (node (ref "U$18") (pin "31") (pinfunction "ANT1_31") (pintype "bidirectional"))
    )
    (net (code "75") (name "Net-(U$18-ANT2)") (class "Default")
      (node (ref "C23") (pin "2") (pinfunction "2_2") (pintype "passive"))
      (node (ref "L2") (pin "2") (pinfunction "2_2") (pintype "passive"))
      (node (ref "U$18") (pin "32") (pinfunction "ANT2_32") (pintype "bidirectional"))
    )
    (net (code "76") (name "Net-(U$18-DCC)") (class "Default")
      (node (ref "L6") (pin "2") (pinfunction "2_2") (pintype "passive"))
      (node (ref "U$18") (pin "2") (pinfunction "DCC_2") (pintype "bidirectional"))
    )
    (net (code "77") (name "Net-(U$18-DEC1)") (class "Default")
      (node (ref "C17") (pin "2") (pinfunction "2_2") (pintype "passive"))
      (node (ref "U$18") (pin "39") (pinfunction "DEC1_39") (pintype "bidirectional"))
    )
    (net (code "78") (name "Net-(U$18-DEC2)") (class "Default")
      (node (ref "C22") (pin "2") (pinfunction "2_2") (pintype "passive"))
      (node (ref "U$18") (pin "29") (pinfunction "DEC2_29") (pintype "bidirectional"))
    )
    (net (code "79") (name "Net-(U$18-VDD_PA)") (class "Default")
      (node (ref "C19") (pin "2") (pinfunction "2_2") (pintype "passive"))
      (node (ref "L1") (pin "1") (pinfunction "1_1") (pintype "passive"))
      (node (ref "U$18") (pin "30") (pinfunction "VDD_PA_30") (pintype "bidirectional"))
    )
    (net (code "80") (name "Net-(U$18-XC1)") (class "Default")
      (node (ref "C16") (pin "2") (pinfunction "2_2") (pintype "passive"))
      (node (ref "U$18") (pin "37") (pinfunction "XC1_37") (pintype "bidirectional"))
      (node (ref "U$4") (pin "OSC2") (pinfunction "OSC2_OSC2") (pintype "bidirectional"))
    )
    (net (code "81") (name "Net-(U$18-XC2)") (class "Default")
      (node (ref "C15") (pin "2") (pinfunction "2_2") (pintype "passive"))
      (node (ref "U$18") (pin "38") (pinfunction "XC2_38") (pintype "bidirectional"))
      (node (ref "U$4") (pin "OSC1") (pinfunction "OSC1_OSC1") (pintype "bidirectional"))
    )
    (net (code "82") (name "Net-(U$40-RF)") (class "Default")
      (node (ref "C25") (pin "1") (pinfunction "1_1") (pintype "passive"))
      (node (ref "C28") (pin "1") (pinfunction "1_1") (pintype "passive"))
      (node (ref "L5") (pin "2") (pinfunction "2_2") (pintype "passive"))
      (node (ref "U$40") (pin "P$2") (pinfunction "RF_P$2") (pintype "bidirectional"))
    )
    (net (code "83") (name "Net-(U1-EN)") (class "Default")
      (node (ref "R25") (pin "1") (pinfunction "1_1") (pintype "passive"))
      (node (ref "U1") (pin "4") (pinfunction "EN_4") (pintype "bidirectional"))
    )
    (net (code "84") (name "Net-(U1-FB)") (class "Default")
      (node (ref "R16") (pin "1") (pinfunction "1_1") (pintype "passive"))
      (node (ref "R23") (pin "2") (pinfunction "2_2") (pintype "passive"))
      (node (ref "U1") (pin "3") (pinfunction "FB_3") (pintype "bidirectional"))
    )
    (net (code "85") (name "Net-(U1-SW)") (class "Default")
      (node (ref "D2") (pin "A") (pinfunction "A_A") (pintype "passive"))
      (node (ref "L3") (pin "2") (pinfunction "2_2") (pintype "passive"))
      (node (ref "U1") (pin "1") (pinfunction "SW_1") (pintype "bidirectional"))
    )
    (net (code "86") (name "Net-(U3-EN)") (class "Default")
      (node (ref "R26") (pin "1") (pinfunction "1_1") (pintype "passive"))
      (node (ref "U3") (pin "4") (pinfunction "EN_4") (pintype "bidirectional"))
    )
    (net (code "87") (name "Net-(U3-FB)") (class "Default")
      (node (ref "R11") (pin "1") (pinfunction "1_1") (pintype "passive"))
      (node (ref "R4") (pin "2") (pinfunction "2_2") (pintype "passive"))
      (node (ref "U3") (pin "3") (pinfunction "FB_3") (pintype "bidirectional"))
    )
    (net (code "88") (name "Net-(U3-SW)") (class "Default")
      (node (ref "D3") (pin "A") (pinfunction "A_A") (pintype "passive"))
      (node (ref "L4") (pin "2") (pinfunction "2_2") (pintype "passive"))
      (node (ref "U3") (pin "1") (pinfunction "SW_1") (pintype "bidirectional"))
    )
    (net (code "89") (name "PORTM1") (class "Default")
      (node (ref "IC5") (pin "2") (pinfunction "1A_2") (pintype "input"))
      (node (ref "U$18") (pin "40") (pinfunction "P0.21_40") (pintype "bidirectional"))
    )
    (net (code "90") (name "PORTM2") (class "Default")
      (node (ref "IC5") (pin "7") (pinfunction "2A_7") (pintype "input"))
      (node (ref "U$18") (pin "41") (pinfunction "P0.22_41") (pintype "bidirectional"))
    )
    (net (code "91") (name "PORTM3") (class "Default")
      (node (ref "IC5") (pin "15") (pinfunction "4A_15") (pintype "input"))
      (node (ref "U$18") (pin "42") (pinfunction "P0.23_42") (pintype "bidirectional"))
    )
    (net (code "92") (name "PORTM4") (class "Default")
      (node (ref "IC5") (pin "10") (pinfunction "3A_10") (pintype "input"))
      (node (ref "U$18") (pin "43") (pinfunction "P0.24_43") (pintype "bidirectional"))
    )
    (net (code "93") (name "PROG1") (class "Default")
      (node (ref "R8") (pin "1") (pinfunction "1_1") (pintype "passive"))
      (node (ref "U$18") (pin "44") (pinfunction "P0.25_44") (pintype "bidirectional"))
      (node (ref "U$27") (pin "1") (pinfunction "1_1") (pintype "bidirectional"))
    )
    (net (code "94") (name "RST") (class "Default")
      (node (ref "R5") (pin "1") (pinfunction "1_1") (pintype "passive"))
      (node (ref "RST") (pin "1") (pinfunction "1_1") (pintype "bidirectional"))
      (node (ref "U$18") (pin "23") (pinfunction "SWDIO/NRESET_23") (pintype "bidirectional"))
      (node (ref "U$6") (pin "1") (pinfunction "1_1") (pintype "bidirectional"))
    )
    (net (code "95") (name "SWDCLK") (class "Default")
      (node (ref "R2") (pin "2") (pinfunction "2_2") (pintype "passive"))
      (node (ref "U$18") (pin "24") (pinfunction "SWDCLK_24") (pintype "bidirectional"))
      (node (ref "U$6") (pin "2") (pinfunction "2_2") (pintype "bidirectional"))
    )
    (net (code "96") (name "TFT") (class "Default")
      (node (ref "R17") (pin "1") (pinfunction "1_1") (pintype "passive"))
      (node (ref "U$18") (pin "3") (pinfunction "P0.30_3") (pintype "bidirectional"))
      (node (ref "U$26") (pin "P$6") (pinfunction "RST_P$6") (pintype "bidirectional"))
    )
    (net (code "97") (name "VCC{slash}2") (class "Default")
      (node (ref "C1") (pin "1") (pinfunction "1_1") (pintype "passive"))
      (node (ref "C13") (pin "1") (pinfunction "1_1") (pintype "passive"))
      (node (ref "IC2") (pin "VCC") (pinfunction "VCC_VCC") (pintype "passive"))
      (node (ref "LED6") (pin "A") (pinfunction "A_A") (pintype "passive"))
      (node (ref "LED7") (pin "A") (pinfunction "A_A") (pintype "passive"))
      (node (ref "R3") (pin "1") (pinfunction "1_1") (pintype "passive"))
      (node (ref "R9") (pin "2") (pinfunction "2_2") (pintype "passive"))
      (node (ref "T2") (pin "3") (pinfunction "C_3") (pintype "passive"))
      (node (ref "U$52") (pin "VUSB") (pinfunction "VBUS_VUSB") (pintype "bidirectional"))
    )
    (net (code "98") (name "unconnected-(U$18-DIE_PAD-PadGND)") (class "Default")
      (node (ref "U$18") (pin "GND") (pinfunction "DIE_PAD_GND") (pintype "bidirectional"))
    )
    (net (code "99") (name "unconnected-(U$26-NC-PadP$1)") (class "Default")
      (node (ref "U$26") (pin "P$1") (pinfunction "NC_P$1") (pintype "bidirectional"))
    )
    (net (code "100") (name "unconnected-(U$26-NC2-PadP$14)") (class "Default")
      (node (ref "U$26") (pin "P$14") (pinfunction "NC2_P$14") (pintype "bidirectional"))
    )
    (net (code "101") (name "unconnected-(U$52-PadID)") (class "Default")
      (node (ref "U$52") (pin "ID") (pinfunction "ID_ID") (pintype "bidirectional"))
    )
    (net (code "102") (name "unconnected-(U1-NC-Pad6)") (class "Default")
      (node (ref "U1") (pin "6") (pinfunction "NC_6") (pintype "bidirectional"))
    )
    (net (code "103") (name "unconnected-(U2-DCD-Pad1)") (class "Default")
      (node (ref "U2") (pin "1") (pinfunction "DCD_1") (pintype "input"))
    )
    (net (code "104") (name "unconnected-(U2-DSR-Pad27)") (class "Default")
      (node (ref "U2") (pin "27") (pinfunction "DSR_27") (pintype "input"))
    )
    (net (code "105") (name "unconnected-(U2-DTR-Pad28)") (class "Default")
      (node (ref "U2") (pin "28") (pinfunction "DTR_28") (pintype "output"))
    )
    (net (code "106") (name "unconnected-(U2-RI-Pad2)") (class "Default")
      (node (ref "U2") (pin "2") (pinfunction "RI_2") (pintype "input"))
    )
    (net (code "107") (name "unconnected-(U2-SUSPEND-Pad12)") (class "Default")
      (node (ref "U2") (pin "12") (pinfunction "SUSPEND_12") (pintype "output"))
    )
    (net (code "108") (name "unconnected-(U2-~{RST}-Pad9)") (class "Default")
      (node (ref "U2") (pin "9") (pinfunction "~{RST}_9") (pintype "bidirectional"))
    )
    (net (code "109") (name "unconnected-(U2-~{SUSPEND}-Pad11)") (class "Default")
      (node (ref "U2") (pin "11") (pinfunction "~{SUSPEND}_11") (pintype "output"))
    )
    (net (code "110") (name "unconnected-(U3-NC-Pad6)") (class "Default")
      (node (ref "U3") (pin "6") (pinfunction "NC_6") (pintype "bidirectional"))
    )
  )
)
